# EFUSE_TPS259251.net
KiCad netlist of a schematic drawn in Altium Designer
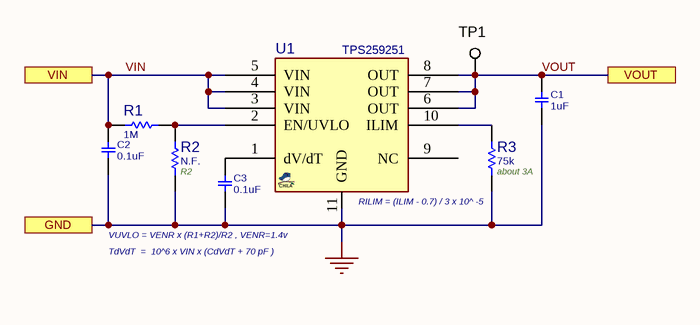
[diagram p0: EFUSE_TPS259251.SchDoc]

(export (version "E")
  (design (tool "Eeschema 10.0.6"))
  (components
    (comp (ref "C1")
      (value "1uF")
      (footprint "C0402")
      (description "CAP, MLCC")
      (fields (field (name "MANF_P#") "CL05A105KO5NNND") (field (name "MANF") "Samsung"))
      (libsource (lib "passive_smd") (part "CAP_SMD_MLCC"))
    )
    (comp (ref "C2")
      (value "0.1uF")
      (footprint "C0402")
      (description "CAP, MLCC")
      (fields (field (name "MANF_P#") "GRM155R61E104") (field (name "MANF") "Murata"))
      (libsource (lib "passive_smd") (part "CAP_SMD_MLCC"))
    )
    (comp (ref "C3")
      (value "0.1uF")
      (footprint "C0402")
      (description "CAP, MLCC")
      (fields (field (name "MANF_P#") "GRM155R61E104") (field (name "MANF") "Murata"))
      (libsource (lib "passive_smd") (part "CAP_SMD_MLCC"))
    )
    (comp (ref "R1")
      (value "1M")
      (footprint "R0402")
      (description "RESISTOR, SMD")
      (libsource (lib "passive_res_smd") (part "RES_SMD"))
    )
    (comp (ref "R2")
      (value "N.F.")
      (footprint "R0402")
      (description "RESISTOR, SMD")
      (libsource (lib "passive_res_smd") (part "RES_SMD"))
    )
    (comp (ref "R3")
      (value "75k")
      (footprint "R0402")
      (description "RESISTOR, SMD")
      (libsource (lib "passive_res_smd") (part "RES_SMD"))
    )
    (comp (ref "TP1")
      (value "TESTPOINT_SMD")
      (footprint "TPSMD_S1")
      (description "TEST POINT")
      (fields (field (name "MANF") "MANF") (field (name "MANF_P#") "MANF_P#"))
      (libsource (lib "test-tp_jumper") (part "TESTPOINT_SMD"))
    )
    (comp (ref "U1")
      (value "TPS259251")
      (footprint "SON50_10T_3030")
      (description "LOAD SW, 5V eFuse, 5A, 4.5~5.5V, 30mOhm")
      (fields (field (name "MANF") "TI") (field (name "MANF_P#") "TPS259251DRCR, TPS259251DRCT"))
      (libsource (lib "power_load_switch") (part "TPS259251_SON10"))
    )
  )
  (nets
    (net (code "1") (name "/VIN") (class "Default")
      (node (ref "C2") (pin "2") (pinfunction "2_2") (pintype "passive"))
      (node (ref "R1") (pin "1") (pinfunction "1_1") (pintype "passive"))
      (node (ref "U1") (pin "3") (pinfunction "VIN_3") (pintype "passive"))
      (node (ref "U1") (pin "4") (pinfunction "VIN_4") (pintype "passive"))
      (node (ref "U1") (pin "5") (pinfunction "VIN_5") (pintype "passive"))
    )
    (net (code "2") (name "/VOUT") (class "Default")
      (node (ref "C1") (pin "2") (pinfunction "2_2") (pintype "passive"))
      (node (ref "TP1") (pin "1") (pinfunction "1_1") (pintype "passive"))
      (node (ref "U1") (pin "6") (pinfunction "OUT_6") (pintype "passive"))
      (node (ref "U1") (pin "7") (pinfunction "OUT_7") (pintype "passive"))
      (node (ref "U1") (pin "8") (pinfunction "OUT_8") (pintype "passive"))
    )
    (net (code "3") (name "GND") (class "Default")
      (node (ref "C1") (pin "1") (pinfunction "1_1") (pintype "passive"))
      (node (ref "C2") (pin "1") (pinfunction "1_1") (pintype "passive"))
      (node (ref "C3") (pin "1") (pinfunction "1_1") (pintype "passive"))
      (node (ref "R2") (pin "1") (pinfunction "1_1") (pintype "passive"))
      (node (ref "R3") (pin "1") (pinfunction "1_1") (pintype "passive"))
      (node (ref "U1") (pin "11") (pinfunction "GND_11") (pintype "power_in"))
    )
    (net (code "4") (name "Net-(U1-EN{slash}UVLO)") (class "Default")
      (node (ref "R1") (pin "2") (pinfunction "2_2") (pintype "passive"))
      (node (ref "R2") (pin "2") (pinfunction "2_2") (pintype "passive"))
      (node (ref "U1") (pin "2") (pinfunction "EN/UVLO_2") (pintype "passive"))
    )
    (net (code "5") (name "Net-(U1-ILIM)") (class "Default")
      (node (ref "R3") (pin "2") (pinfunction "2_2") (pintype "passive"))
      (node (ref "U1") (pin "10") (pinfunction "ILIM_10") (pintype "passive"))
    )
    (net (code "6") (name "Net-(U1-dV{slash}dT)") (class "Default")
      (node (ref "C3") (pin "2") (pinfunction "2_2") (pintype "passive"))
      (node (ref "U1") (pin "1") (pinfunction "dV/dT_1") (pintype "passive"))
    )
    (net (code "7") (name "unconnected-(U1-NC-Pad9)") (class "Default")
      (node (ref "U1") (pin "9") (pinfunction "NC_9") (pintype "passive"))
    )
  )
)
